# Microcontroller.net
KiCad netlist of a schematic drawn in Altium Designer
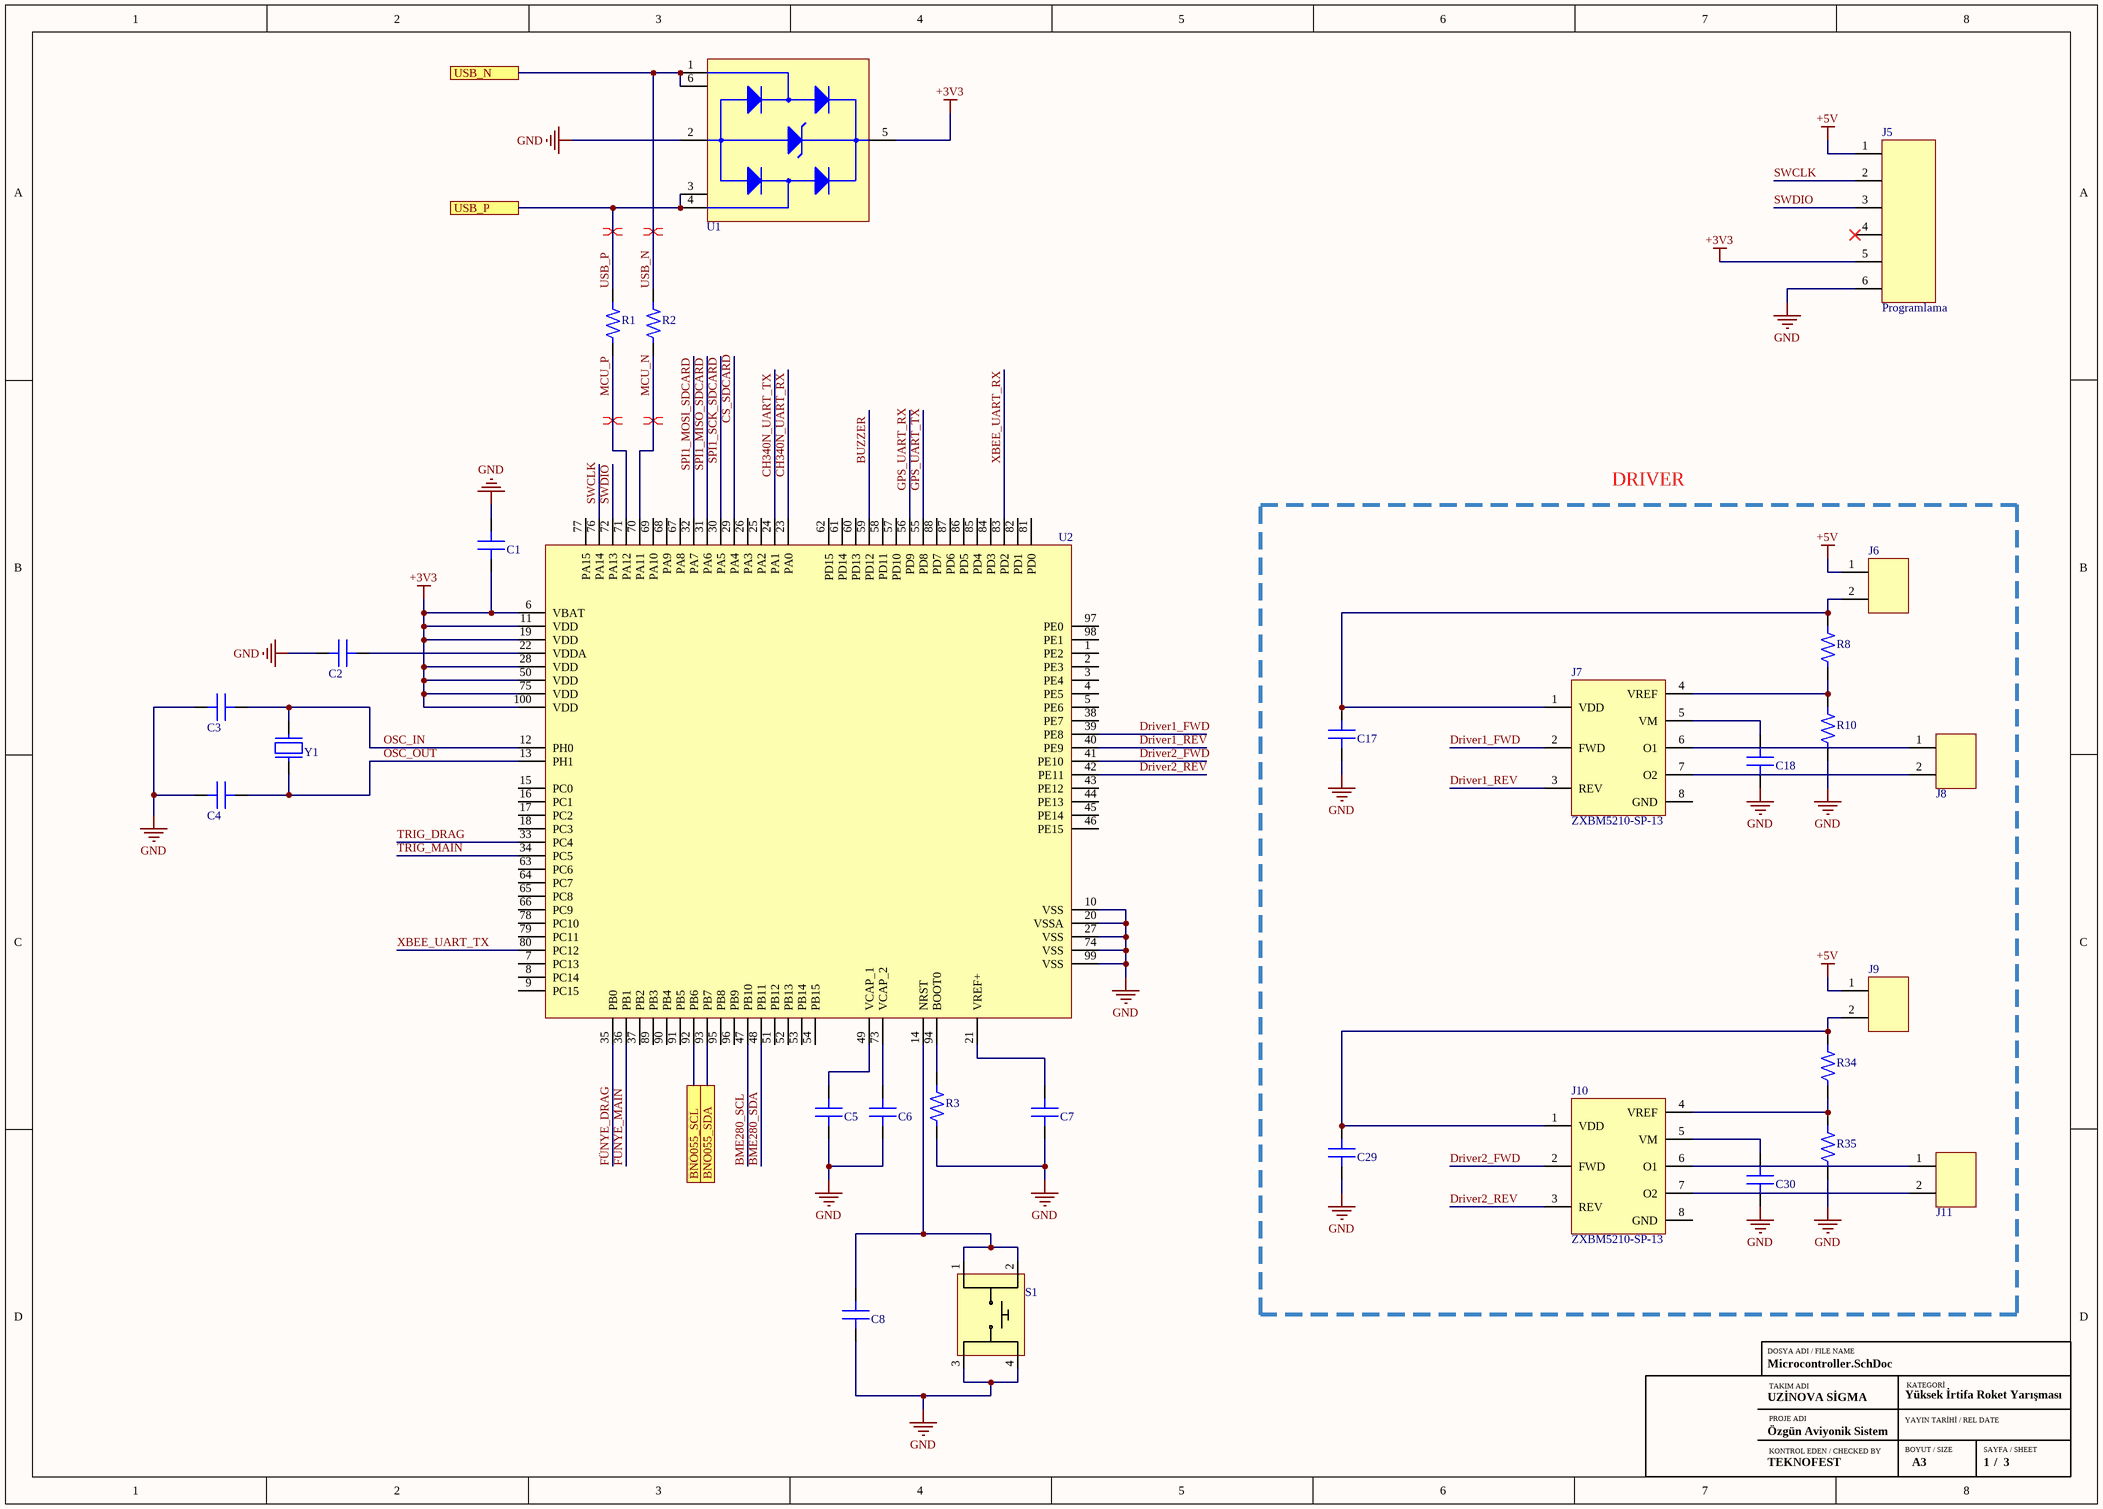
[diagram p0: Microcontroller.SchDoc]

(export (version "E")
  (design (tool "Eeschema 10.0.6"))
  (components
    (comp (ref "C1")
      (value "CAP CER 1uF 0805")
      (footprint "CAP_0805")
      (libsource (lib "ROKET_LIBRARY") (part "CAP CER 1uF 0805"))
    )
    (comp (ref "C2")
      (value "CAP CER 10nF 0805")
      (footprint "CAP_0805")
      (libsource (lib "ROKET_LIBRARY") (part "CAP CER 10nF 0805"))
    )
    (comp (ref "C3")
      (value "CAP CER 20pF 0805")
      (footprint "CAP_0805")
      (libsource (lib "ROKET_LIBRARY") (part "CAP CER 20pF 0805"))
    )
    (comp (ref "C4")
      (value "CAP CER 20pF 0805")
      (footprint "CAP_0805")
      (libsource (lib "ROKET_LIBRARY") (part "CAP CER 20pF 0805"))
    )
    (comp (ref "C5")
      (value "CAP CER 2.2uF 0805")
      (footprint "CAP_0805")
      (libsource (lib "ROKET_LIBRARY") (part "CAP CER 2.2uF 0805"))
    )
    (comp (ref "C6")
      (value "CAP CER 2.2uF 0805")
      (footprint "CAP_0805")
      (libsource (lib "ROKET_LIBRARY") (part "CAP CER 2.2uF 0805"))
    )
    (comp (ref "C7")
      (value "CAP CER 10nF 0805")
      (footprint "CAP_0805")
      (libsource (lib "ROKET_LIBRARY") (part "CAP CER 10nF 0805"))
    )
    (comp (ref "C8")
      (value "CAP CER 0.1uF 0805")
      (footprint "CAP_0805")
      (libsource (lib "ROKET_LIBRARY") (part "CAP CER 0.1uF 0805"))
    )
    (comp (ref "C17")
      (value "CAP CER 1uF 0805")
      (footprint "CAP_0805")
      (libsource (lib "ROKET_LIBRARY") (part "CAP CER 1uF 0805"))
    )
    (comp (ref "C18")
      (value "CAP CER 10uF 0805")
      (footprint "CAP_0805")
      (libsource (lib "ROKET_LIBRARY") (part "CAP CER 10uF 0805"))
    )
    (comp (ref "C29")
      (value "CAP CER 1uF 0805")
      (footprint "CAP_0805")
      (libsource (lib "ROKET_LIBRARY") (part "CAP CER 1uF 0805"))
    )
    (comp (ref "C30")
      (value "CAP CER 10uF 0805")
      (footprint "CAP_0805")
      (libsource (lib "ROKET_LIBRARY") (part "CAP CER 10uF 0805"))
    )
    (comp (ref "J5")
      (value "Programlama")
      (footprint "PPTC061LFBN-RC")
      (libsource (lib "ROKET_LIBRARY") (part "Programlama"))
    )
    (comp (ref "J6")
      (value "Mike Connector")
      (footprint "MIKE CONNECTOR")
      (libsource (lib "ROKET_LIBRARY") (part "Mike Connector"))
    )
    (comp (ref "J7")
      (value "ZXBM5210-SP-13")
      (footprint "SO-8EP")
      (description "ZXBM5210 Series 18 V 1.5 A Reversible DC Motor Drive with Speed Control-SOIC-8EP")
      (fields (field (name "MANUFACTURER") "Diodes"))
      (libsource (lib "Roket_Library") (part "Driver"))
    )
    (comp (ref "J8")
      (value "HEADER x2")
      (footprint "HEADER x2")
      (description "Conn Screw Type Terminal Block 2 POS 3.5mm Solder ST Thru-Hole 10A")
      (fields
        (field (name "MANUFACTURER") "On-Shore Technology")
        (field (name "MANUFACTURER PART NUMBER") "OSTTE020104")
      )
      (libsource (lib "ROKET_LIBRARY") (part "HEADER x2"))
    )
    (comp (ref "J9")
      (value "Mike Connector")
      (footprint "MIKE CONNECTOR")
      (libsource (lib "ROKET_LIBRARY") (part "Mike Connector"))
    )
    (comp (ref "J10")
      (value "ZXBM5210-SP-13")
      (footprint "SO-8EP")
      (description "ZXBM5210 Series 18 V 1.5 A Reversible DC Motor Drive with Speed Control-SOIC-8EP")
      (fields (field (name "MANUFACTURER") "Diodes"))
      (libsource (lib "Roket_Library") (part "Driver"))
    )
    (comp (ref "J11")
      (value "HEADER x2")
      (footprint "HEADER x2")
      (description "Conn Screw Type Terminal Block 2 POS 3.5mm Solder ST Thru-Hole 10A")
      (fields
        (field (name "MANUFACTURER") "On-Shore Technology")
        (field (name "MANUFACTURER PART NUMBER") "OSTTE020104")
      )
      (libsource (lib "ROKET_LIBRARY") (part "HEADER x2"))
    )
    (comp (ref "R1")
      (value "RES 15 OHM 0805")
      (footprint "RES_0805")
      (libsource (lib "ROKET_LIBRARY") (part "RES 15 OHM 0805"))
    )
    (comp (ref "R2")
      (value "RES 15 OHM 0805")
      (footprint "RES_0805")
      (libsource (lib "ROKET_LIBRARY") (part "RES 15 OHM 0805"))
    )
    (comp (ref "R3")
      (value "RES 10K OHM 0805")
      (footprint "RES_0805")
      (libsource (lib "ROKET_LIBRARY") (part "RES 10K OHM 0805"))
    )
    (comp (ref "R8")
      (value "RES 1K OHM 0805")
      (footprint "RES_0805")
      (libsource (lib "ROKET_LIBRARY") (part "RES 1K OHM 0805"))
    )
    (comp (ref "R10")
      (value "RES 1K OHM 0805")
      (footprint "RES_0805")
      (libsource (lib "ROKET_LIBRARY") (part "RES 1K OHM 0805"))
    )
    (comp (ref "R34")
      (value "RES 1K OHM 0805")
      (footprint "RES_0805")
      (libsource (lib "ROKET_LIBRARY") (part "RES 1K OHM 0805"))
    )
    (comp (ref "R35")
      (value "RES 1K OHM 0805")
      (footprint "RES_0805")
      (libsource (lib "ROKET_LIBRARY") (part "RES 1K OHM 0805"))
    )
    (comp (ref "S1")
      (value "PTS815 SJG 250 SMTR LFS")
      (footprint "BUTTON")
      (description "Switch Tactile N.O. SPST Button J-Bend 0.05A 12VDC 3.92N SMD T/R")
      (fields
        (field (name "MANUFACTURER") "ITT C&K")
        (field (name "MANUFACTURER PART NUMBER") "PTS815SJG250SMTRLFS")
      )
      (libsource (lib "ROKET_LIBRARY") (part "BUTTON"))
    )
    (comp (ref "U1")
      (value "USBLC6-2SC6")
      (footprint "SOT-23-6L")
      (description "TVS DIODE 5.25VWM 17VC SOT23-6")
      (fields (field (name "MANUFACTURER") "STMicroelectronics"))
      (libsource (lib "ROKET_LIBRARY") (part "USB PROTECTION"))
    )
    (comp (ref "U2")
      (value "STM32F407VGT6")
      (footprint "LQFP-100")
      (description "IC MCU 32BIT 1MB FLASH 100LQFP")
      (fields (field (name "MANUFACTURER") "STMicroelectronics"))
      (libsource (lib "ROKET_LIBRARY") (part "STM32F407VGT6"))
    )
    (comp (ref "Y1")
      (value "CRYSTAL 32.7680KHZ 12.5PF SMD")
      (footprint "CRYSTAL_ABS05")
      (description "Crystal 0.032768MHz ±20ppm (Tol) 12.5pF Flexural 90000Ohm 2-Pin CSMD T/R")
      (fields
        (field (name "MANUFACTURER") "Abracon")
        (field (name "MANUFACTURER PART NUMBER") "ABS05-32.768KHZ-T")
      )
      (libsource (lib "ROKET_LIBRARY") (part "CRYSTAL"))
    )
  )
  (nets
    (net (code "1") (name "+3V3") (class "Default")
      (node (ref "C1") (pin "1") (pinfunction "1_1") (pintype "passive"))
      (node (ref "J5") (pin "5") (pintype "passive"))
      (node (ref "U1") (pin "5") (pinfunction "VBUS_5") (pintype "power_in"))
      (node (ref "U2") (pin "100") (pinfunction "VDD_100") (pintype "passive"))
      (node (ref "U2") (pin "11") (pinfunction "VDD_11") (pintype "passive"))
      (node (ref "U2") (pin "19") (pinfunction "VDD_19") (pintype "passive"))
      (node (ref "U2") (pin "28") (pinfunction "VDD_28") (pintype "passive"))
      (node (ref "U2") (pin "50") (pinfunction "VDD_50") (pintype "passive"))
      (node (ref "U2") (pin "6") (pinfunction "VBAT_6") (pintype "passive"))
      (node (ref "U2") (pin "75") (pinfunction "VDD_75") (pintype "passive"))
    )
    (net (code "2") (name "+5V") (class "Default")
      (node (ref "J5") (pin "1") (pintype "passive"))
      (node (ref "J6") (pin "1") (pintype "passive"))
      (node (ref "J9") (pin "1") (pintype "passive"))
    )
    (net (code "3") (name "/BME280_SCL") (class "Default")
      (node (ref "U2") (pin "47") (pinfunction "PB10_47") (pintype "passive"))
    )
    (net (code "4") (name "/BME280_SDA") (class "Default")
      (node (ref "U2") (pin "48") (pinfunction "PB11_48") (pintype "passive"))
    )
    (net (code "5") (name "/BNO055_SCL") (class "Default")
      (node (ref "U2") (pin "92") (pinfunction "PB6_92") (pintype "passive"))
    )
    (net (code "6") (name "/BNO055_SDA") (class "Default")
      (node (ref "U2") (pin "93") (pinfunction "PB7_93") (pintype "passive"))
    )
    (net (code "7") (name "/BUZZER") (class "Default")
      (node (ref "U2") (pin "59") (pinfunction "PD12_59") (pintype "passive"))
    )
    (net (code "8") (name "/CH340N_UART_RX") (class "Default")
      (node (ref "U2") (pin "23") (pinfunction "PA0_23") (pintype "passive"))
    )
    (net (code "9") (name "/CH340N_UART_TX") (class "Default")
      (node (ref "U2") (pin "24") (pinfunction "PA1_24") (pintype "passive"))
    )
    (net (code "10") (name "/CS_SDCARD") (class "Default")
      (node (ref "U2") (pin "29") (pinfunction "PA4_29") (pintype "passive"))
    )
    (net (code "11") (name "/Driver1_FWD") (class "Default")
      (node (ref "J7") (pin "2") (pinfunction "FWD_2") (pintype "passive"))
      (node (ref "U2") (pin "39") (pinfunction "PE8_39") (pintype "passive"))
    )
    (net (code "12") (name "/Driver1_REV") (class "Default")
      (node (ref "J7") (pin "3") (pinfunction "REV_3") (pintype "passive"))
      (node (ref "U2") (pin "40") (pinfunction "PE9_40") (pintype "passive"))
    )
    (net (code "13") (name "/Driver2_FWD") (class "Default")
      (node (ref "J10") (pin "2") (pinfunction "FWD_2") (pintype "passive"))
      (node (ref "U2") (pin "41") (pinfunction "PE10_41") (pintype "passive"))
    )
    (net (code "14") (name "/Driver2_REV") (class "Default")
      (node (ref "J10") (pin "3") (pinfunction "REV_3") (pintype "passive"))
      (node (ref "U2") (pin "42") (pinfunction "PE11_42") (pintype "passive"))
    )
    (net (code "15") (name "/FÜNYE_DRAG") (class "Default")
      (node (ref "U2") (pin "35") (pinfunction "PB0_35") (pintype "passive"))
    )
    (net (code "16") (name "/FÜNYE_MAIN") (class "Default")
      (node (ref "U2") (pin "36") (pinfunction "PB1_36") (pintype "passive"))
    )
    (net (code "17") (name "/GPS_UART_RX") (class "Default")
      (node (ref "U2") (pin "56") (pinfunction "PD9_56") (pintype "passive"))
    )
    (net (code "18") (name "/GPS_UART_TX") (class "Default")
      (node (ref "U2") (pin "55") (pinfunction "PD8_55") (pintype "passive"))
    )
    (net (code "19") (name "/MCU_N") (class "Default")
      (node (ref "R2") (pin "1") (pinfunction "1_1") (pintype "passive"))
      (node (ref "U2") (pin "70") (pinfunction "PA11_70") (pintype "passive"))
    )
    (net (code "20") (name "/MCU_P") (class "Default")
      (node (ref "R1") (pin "1") (pinfunction "1_1") (pintype "passive"))
      (node (ref "U2") (pin "71") (pinfunction "PA12_71") (pintype "passive"))
    )
    (net (code "21") (name "/OSC_IN") (class "Default")
      (node (ref "C3") (pin "2") (pinfunction "2_2") (pintype "passive"))
      (node (ref "U2") (pin "12") (pinfunction "PH0_12") (pintype "passive"))
      (node (ref "Y1") (pin "2") (pinfunction "2_2") (pintype "passive"))
    )
    (net (code "22") (name "/OSC_OUT") (class "Default")
      (node (ref "C4") (pin "2") (pinfunction "2_2") (pintype "passive"))
      (node (ref "U2") (pin "13") (pinfunction "PH1_13") (pintype "passive"))
      (node (ref "Y1") (pin "1") (pinfunction "1_1") (pintype "passive"))
    )
    (net (code "23") (name "/SPI1_MISO_SDCARD") (class "Default")
      (node (ref "U2") (pin "31") (pinfunction "PA6_31") (pintype "passive"))
    )
    (net (code "24") (name "/SPI1_MOSI_SDCARD") (class "Default")
      (node (ref "U2") (pin "32") (pinfunction "PA7_32") (pintype "passive"))
    )
    (net (code "25") (name "/SPI1_SCK_SDCARD") (class "Default")
      (node (ref "U2") (pin "30") (pinfunction "PA5_30") (pintype "passive"))
    )
    (net (code "26") (name "/SWCLK") (class "Default")
      (node (ref "J5") (pin "2") (pintype "passive"))
      (node (ref "U2") (pin "76") (pinfunction "PA14_76") (pintype "passive"))
    )
    (net (code "27") (name "/SWDIO") (class "Default")
      (node (ref "J5") (pin "3") (pintype "passive"))
      (node (ref "U2") (pin "72") (pinfunction "PA13_72") (pintype "passive"))
    )
    (net (code "28") (name "/TRIG_DRAG") (class "Default")
      (node (ref "U2") (pin "33") (pinfunction "PC4_33") (pintype "passive"))
    )
    (net (code "29") (name "/TRIG_MAIN") (class "Default")
      (node (ref "U2") (pin "34") (pinfunction "PC5_34") (pintype "passive"))
    )
    (net (code "30") (name "/USB_N") (class "Default")
      (node (ref "R2") (pin "2") (pinfunction "2_2") (pintype "passive"))
      (node (ref "U1") (pin "1") (pinfunction "I/O1_IN_1") (pintype "passive"))
      (node (ref "U1") (pin "6") (pinfunction "I/O1_OUT_6") (pintype "passive"))
    )
    (net (code "31") (name "/USB_P") (class "Default")
      (node (ref "R1") (pin "2") (pinfunction "2_2") (pintype "passive"))
      (node (ref "U1") (pin "3") (pinfunction "I/O2_IN_3") (pintype "passive"))
      (node (ref "U1") (pin "4") (pinfunction "I/O2_OUT_4") (pintype "passive"))
    )
    (net (code "32") (name "/XBEE_UART_RX") (class "Default")
      (node (ref "U2") (pin "83") (pinfunction "PD2_83") (pintype "passive"))
    )
    (net (code "33") (name "/XBEE_UART_TX") (class "Default")
      (node (ref "U2") (pin "80") (pinfunction "PC12_80") (pintype "passive"))
    )
    (net (code "34") (name "GND") (class "Default")
      (node (ref "C1") (pin "2") (pinfunction "2_2") (pintype "passive"))
      (node (ref "C17") (pin "1") (pinfunction "1_1") (pintype "passive"))
      (node (ref "C18") (pin "1") (pinfunction "1_1") (pintype "passive"))
      (node (ref "C2") (pin "1") (pinfunction "1_1") (pintype "passive"))
      (node (ref "C29") (pin "1") (pinfunction "1_1") (pintype "passive"))
      (node (ref "C3") (pin "1") (pinfunction "1_1") (pintype "passive"))
      (node (ref "C30") (pin "1") (pinfunction "1_1") (pintype "passive"))
      (node (ref "C4") (pin "1") (pinfunction "1_1") (pintype "passive"))
      (node (ref "C5") (pin "1") (pinfunction "1_1") (pintype "passive"))
      (node (ref "C6") (pin "1") (pinfunction "1_1") (pintype "passive"))
      (node (ref "C7") (pin "1") (pinfunction "1_1") (pintype "passive"))
      (node (ref "C8") (pin "1") (pinfunction "1_1") (pintype "passive"))
      (node (ref "J5") (pin "6") (pintype "passive"))
      (node (ref "R10") (pin "1") (pinfunction "1_1") (pintype "passive"))
      (node (ref "R3") (pin "1") (pinfunction "1_1") (pintype "passive"))
      (node (ref "R35") (pin "1") (pinfunction "1_1") (pintype "passive"))
      (node (ref "S1") (pin "3") (pinfunction "3_3") (pintype "passive"))
      (node (ref "S1") (pin "4") (pinfunction "4_4") (pintype "passive"))
      (node (ref "U1") (pin "2") (pinfunction "GND_2") (pintype "power_in"))
      (node (ref "U2") (pin "10") (pinfunction "VSS_10") (pintype "passive"))
      (node (ref "U2") (pin "20") (pinfunction "VSSA_20") (pintype "passive"))
      (node (ref "U2") (pin "27") (pinfunction "VSS_27") (pintype "passive"))
      (node (ref "U2") (pin "74") (pinfunction "VSS_74") (pintype "passive"))
      (node (ref "U2") (pin "99") (pinfunction "VSS_99") (pintype "passive"))
    )
    (net (code "35") (name "Net-(J7-O1)") (class "Default")
      (node (ref "J7") (pin "6") (pinfunction "O1_6") (pintype "passive"))
      (node (ref "J8") (pin "1") (pinfunction "1_1") (pintype "passive"))
    )
    (net (code "36") (name "Net-(J7-O2)") (class "Default")
      (node (ref "J7") (pin "7") (pinfunction "O2_7") (pintype "passive"))
      (node (ref "J8") (pin "2") (pinfunction "2_2") (pintype "passive"))
    )
    (net (code "37") (name "Net-(J7-VDD)") (class "Default")
      (node (ref "C17") (pin "2") (pinfunction "2_2") (pintype "passive"))
      (node (ref "J6") (pin "2") (pintype "passive"))
      (node (ref "J7") (pin "1") (pinfunction "VDD_1") (pintype "passive"))
      (node (ref "R8") (pin "2") (pinfunction "2_2") (pintype "passive"))
    )
    (net (code "38") (name "Net-(J7-VM)") (class "Default")
      (node (ref "C18") (pin "2") (pinfunction "2_2") (pintype "passive"))
      (node (ref "J7") (pin "5") (pinfunction "VM_5") (pintype "passive"))
    )
    (net (code "39") (name "Net-(J7-VREF)") (class "Default")
      (node (ref "J7") (pin "4") (pinfunction "VREF_4") (pintype "passive"))
      (node (ref "R10") (pin "2") (pinfunction "2_2") (pintype "passive"))
      (node (ref "R8") (pin "1") (pinfunction "1_1") (pintype "passive"))
    )
    (net (code "40") (name "Net-(J10-O1)") (class "Default")
      (node (ref "J10") (pin "6") (pinfunction "O1_6") (pintype "passive"))
      (node (ref "J11") (pin "1") (pinfunction "1_1") (pintype "passive"))
    )
    (net (code "41") (name "Net-(J10-O2)") (class "Default")
      (node (ref "J10") (pin "7") (pinfunction "O2_7") (pintype "passive"))
      (node (ref "J11") (pin "2") (pinfunction "2_2") (pintype "passive"))
    )
    (net (code "42") (name "Net-(J10-VDD)") (class "Default")
      (node (ref "C29") (pin "2") (pinfunction "2_2") (pintype "passive"))
      (node (ref "J10") (pin "1") (pinfunction "VDD_1") (pintype "passive"))
      (node (ref "J9") (pin "2") (pintype "passive"))
      (node (ref "R34") (pin "2") (pinfunction "2_2") (pintype "passive"))
    )
    (net (code "43") (name "Net-(J10-VM)") (class "Default")
      (node (ref "C30") (pin "2") (pinfunction "2_2") (pintype "passive"))
      (node (ref "J10") (pin "5") (pinfunction "VM_5") (pintype "passive"))
    )
    (net (code "44") (name "Net-(J10-VREF)") (class "Default")
      (node (ref "J10") (pin "4") (pinfunction "VREF_4") (pintype "passive"))
      (node (ref "R34") (pin "1") (pinfunction "1_1") (pintype "passive"))
      (node (ref "R35") (pin "2") (pinfunction "2_2") (pintype "passive"))
    )
    (net (code "45") (name "Net-(U2-BOOT0)") (class "Default")
      (node (ref "R3") (pin "2") (pinfunction "2_2") (pintype "passive"))
      (node (ref "U2") (pin "94") (pinfunction "BOOT0_94") (pintype "passive"))
    )
    (net (code "46") (name "Net-(U2-NRST)") (class "Default")
      (node (ref "C8") (pin "2") (pinfunction "2_2") (pintype "passive"))
      (node (ref "S1") (pin "1") (pinfunction "1_1") (pintype "passive"))
      (node (ref "S1") (pin "2") (pinfunction "2_2") (pintype "passive"))
      (node (ref "U2") (pin "14") (pinfunction "NRST_14") (pintype "passive"))
    )
    (net (code "47") (name "Net-(U2-VCAP_1)") (class "Default")
      (node (ref "C5") (pin "2") (pinfunction "2_2") (pintype "passive"))
      (node (ref "U2") (pin "49") (pinfunction "VCAP_1_49") (pintype "passive"))
    )
    (net (code "48") (name "Net-(U2-VCAP_2)") (class "Default")
      (node (ref "C6") (pin "2") (pinfunction "2_2") (pintype "passive"))
      (node (ref "U2") (pin "73") (pinfunction "VCAP_2_73") (pintype "passive"))
    )
    (net (code "49") (name "Net-(U2-VDDA)") (class "Default")
      (node (ref "C2") (pin "2") (pinfunction "2_2") (pintype "passive"))
      (node (ref "U2") (pin "22") (pinfunction "VDDA_22") (pintype "passive"))
    )
    (net (code "50") (name "Net-(U2-VREF+)") (class "Default")
      (node (ref "C7") (pin "2") (pinfunction "2_2") (pintype "passive"))
      (node (ref "U2") (pin "21") (pinfunction "VREF+_21") (pintype "passive"))
    )
    (net (code "51") (name "unconnected-(J5-Pad4)") (class "Default")
      (node (ref "J5") (pin "4") (pintype "passive+no_connect"))
    )
    (net (code "52") (name "unconnected-(J7-GND-Pad8)") (class "Default")
      (node (ref "J7") (pin "8") (pinfunction "GND_8") (pintype "passive"))
    )
    (net (code "53") (name "unconnected-(J10-GND-Pad8)") (class "Default")
      (node (ref "J10") (pin "8") (pinfunction "GND_8") (pintype "passive"))
    )
    (net (code "54") (name "unconnected-(U2-PA2-Pad25)") (class "Default")
      (node (ref "U2") (pin "25") (pinfunction "PA2_25") (pintype "passive"))
    )
    (net (code "55") (name "unconnected-(U2-PA3-Pad26)") (class "Default")
      (node (ref "U2") (pin "26") (pinfunction "PA3_26") (pintype "passive"))
    )
    (net (code "56") (name "unconnected-(U2-PA8-Pad67)") (class "Default")
      (node (ref "U2") (pin "67") (pinfunction "PA8_67") (pintype "passive"))
    )
    (net (code "57") (name "unconnected-(U2-PA9-Pad68)") (class "Default")
      (node (ref "U2") (pin "68") (pinfunction "PA9_68") (pintype "passive"))
    )
    (net (code "58") (name "unconnected-(U2-PA10-Pad69)") (class "Default")
      (node (ref "U2") (pin "69") (pinfunction "PA10_69") (pintype "passive"))
    )
    (net (code "59") (name "unconnected-(U2-PA15-Pad77)") (class "Default")
      (node (ref "U2") (pin "77") (pinfunction "PA15_77") (pintype "passive"))
    )
    (net (code "60") (name "unconnected-(U2-PB2-Pad37)") (class "Default")
      (node (ref "U2") (pin "37") (pinfunction "PB2_37") (pintype "passive"))
    )
    (net (code "61") (name "unconnected-(U2-PB3-Pad89)") (class "Default")
      (node (ref "U2") (pin "89") (pinfunction "PB3_89") (pintype "passive"))
    )
    (net (code "62") (name "unconnected-(U2-PB4-Pad90)") (class "Default")
      (node (ref "U2") (pin "90") (pinfunction "PB4_90") (pintype "passive"))
    )
    (net (code "63") (name "unconnected-(U2-PB5-Pad91)") (class "Default")
      (node (ref "U2") (pin "91") (pinfunction "PB5_91") (pintype "passive"))
    )
    (net (code "64") (name "unconnected-(U2-PB8-Pad95)") (class "Default")
      (node (ref "U2") (pin "95") (pinfunction "PB8_95") (pintype "passive"))
    )
    (net (code "65") (name "unconnected-(U2-PB9-Pad96)") (class "Default")
      (node (ref "U2") (pin "96") (pinfunction "PB9_96") (pintype "passive"))
    )
    (net (code "66") (name "unconnected-(U2-PB12-Pad51)") (class "Default")
      (node (ref "U2") (pin "51") (pinfunction "PB12_51") (pintype "passive"))
    )
    (net (code "67") (name "unconnected-(U2-PB13-Pad52)") (class "Default")
      (node (ref "U2") (pin "52") (pinfunction "PB13_52") (pintype "passive"))
    )
    (net (code "68") (name "unconnected-(U2-PB14-Pad53)") (class "Default")
      (node (ref "U2") (pin "53") (pinfunction "PB14_53") (pintype "passive"))
    )
    (net (code "69") (name "unconnected-(U2-PB15-Pad54)") (class "Default")
      (node (ref "U2") (pin "54") (pinfunction "PB15_54") (pintype "passive"))
    )
    (net (code "70") (name "unconnected-(U2-PC0-Pad15)") (class "Default")
      (node (ref "U2") (pin "15") (pinfunction "PC0_15") (pintype "passive"))
    )
    (net (code "71") (name "unconnected-(U2-PC1-Pad16)") (class "Default")
      (node (ref "U2") (pin "16") (pinfunction "PC1_16") (pintype "passive"))
    )
    (net (code "72") (name "unconnected-(U2-PC2-Pad17)") (class "Default")
      (node (ref "U2") (pin "17") (pinfunction "PC2_17") (pintype "passive"))
    )
    (net (code "73") (name "unconnected-(U2-PC3-Pad18)") (class "Default")
      (node (ref "U2") (pin "18") (pinfunction "PC3_18") (pintype "passive"))
    )
    (net (code "74") (name "unconnected-(U2-PC6-Pad63)") (class "Default")
      (node (ref "U2") (pin "63") (pinfunction "PC6_63") (pintype "passive"))
    )
    (net (code "75") (name "unconnected-(U2-PC7-Pad64)") (class "Default")
      (node (ref "U2") (pin "64") (pinfunction "PC7_64") (pintype "passive"))
    )
    (net (code "76") (name "unconnected-(U2-PC8-Pad65)") (class "Default")
      (node (ref "U2") (pin "65") (pinfunction "PC8_65") (pintype "passive"))
    )
    (net (code "77") (name "unconnected-(U2-PC9-Pad66)") (class "Default")
      (node (ref "U2") (pin "66") (pinfunction "PC9_66") (pintype "passive"))
    )
    (net (code "78") (name "unconnected-(U2-PC10-Pad78)") (class "Default")
      (node (ref "U2") (pin "78") (pinfunction "PC10_78") (pintype "passive"))
    )
    (net (code "79") (name "unconnected-(U2-PC11-Pad79)") (class "Default")
      (node (ref "U2") (pin "79") (pinfunction "PC11_79") (pintype "passive"))
    )
    (net (code "80") (name "unconnected-(U2-PC13-Pad7)") (class "Default")
      (node (ref "U2") (pin "7") (pinfunction "PC13_7") (pintype "passive"))
    )
    (net (code "81") (name "unconnected-(U2-PC14-Pad8)") (class "Default")
      (node (ref "U2") (pin "8") (pinfunction "PC14_8") (pintype "passive"))
    )
    (net (code "82") (name "unconnected-(U2-PC15-Pad9)") (class "Default")
      (node (ref "U2") (pin "9") (pinfunction "PC15_9") (pintype "passive"))
    )
    (net (code "83") (name "unconnected-(U2-PD0-Pad81)") (class "Default")
      (node (ref "U2") (pin "81") (pinfunction "PD0_81") (pintype "passive"))
    )
    (net (code "84") (name "unconnected-(U2-PD1-Pad82)") (class "Default")
      (node (ref "U2") (pin "82") (pinfunction "PD1_82") (pintype "passive"))
    )
    (net (code "85") (name "unconnected-(U2-PD3-Pad84)") (class "Default")
      (node (ref "U2") (pin "84") (pinfunction "PD3_84") (pintype "passive"))
    )
    (net (code "86") (name "unconnected-(U2-PD4-Pad85)") (class "Default")
      (node (ref "U2") (pin "85") (pinfunction "PD4_85") (pintype "passive"))
    )
    (net (code "87") (name "unconnected-(U2-PD5-Pad86)") (class "Default")
      (node (ref "U2") (pin "86") (pinfunction "PD5_86") (pintype "passive"))
    )
    (net (code "88") (name "unconnected-(U2-PD6-Pad87)") (class "Default")
      (node (ref "U2") (pin "87") (pinfunction "PD6_87") (pintype "passive"))
    )
    (net (code "89") (name "unconnected-(U2-PD7-Pad88)") (class "Default")
      (node (ref "U2") (pin "88") (pinfunction "PD7_88") (pintype "passive"))
    )
    (net (code "90") (name "unconnected-(U2-PD10-Pad57)") (class "Default")
      (node (ref "U2") (pin "57") (pinfunction "PD10_57") (pintype "passive"))
    )
    (net (code "91") (name "unconnected-(U2-PD11-Pad58)") (class "Default")
      (node (ref "U2") (pin "58") (pinfunction "PD11_58") (pintype "passive"))
    )
    (net (code "92") (name "unconnected-(U2-PD13-Pad60)") (class "Default")
      (node (ref "U2") (pin "60") (pinfunction "PD13_60") (pintype "passive"))
    )
    (net (code "93") (name "unconnected-(U2-PD14-Pad61)") (class "Default")
      (node (ref "U2") (pin "61") (pinfunction "PD14_61") (pintype "passive"))
    )
    (net (code "94") (name "unconnected-(U2-PD15-Pad62)") (class "Default")
      (node (ref "U2") (pin "62") (pinfunction "PD15_62") (pintype "passive"))
    )
    (net (code "95") (name "unconnected-(U2-PE0-Pad97)") (class "Default")
      (node (ref "U2") (pin "97") (pinfunction "PE0_97") (pintype "passive"))
    )
    (net (code "96") (name "unconnected-(U2-PE1-Pad98)") (class "Default")
      (node (ref "U2") (pin "98") (pinfunction "PE1_98") (pintype "passive"))
    )
    (net (code "97") (name "unconnected-(U2-PE2-Pad1)") (class "Default")
      (node (ref "U2") (pin "1") (pinfunction "PE2_1") (pintype "passive"))
    )
    (net (code "98") (name "unconnected-(U2-PE3-Pad2)") (class "Default")
      (node (ref "U2") (pin "2") (pinfunction "PE3_2") (pintype "passive"))
    )
    (net (code "99") (name "unconnected-(U2-PE4-Pad3)") (class "Default")
      (node (ref "U2") (pin "3") (pinfunction "PE4_3") (pintype "passive"))
    )
    (net (code "100") (name "unconnected-(U2-PE5-Pad4)") (class "Default")
      (node (ref "U2") (pin "4") (pinfunction "PE5_4") (pintype "passive"))
    )
    (net (code "101") (name "unconnected-(U2-PE6-Pad5)") (class "Default")
      (node (ref "U2") (pin "5") (pinfunction "PE6_5") (pintype "passive"))
    )
    (net (code "102") (name "unconnected-(U2-PE7-Pad38)") (class "Default")
      (node (ref "U2") (pin "38") (pinfunction "PE7_38") (pintype "passive"))
    )
    (net (code "103") (name "unconnected-(U2-PE12-Pad43)") (class "Default")
      (node (ref "U2") (pin "43") (pinfunction "PE12_43") (pintype "passive"))
    )
    (net (code "104") (name "unconnected-(U2-PE13-Pad44)") (class "Default")
      (node (ref "U2") (pin "44") (pinfunction "PE13_44") (pintype "passive"))
    )
    (net (code "105") (name "unconnected-(U2-PE14-Pad45)") (class "Default")
      (node (ref "U2") (pin "45") (pinfunction "PE14_45") (pintype "passive"))
    )
    (net (code "106") (name "unconnected-(U2-PE15-Pad46)") (class "Default")
      (node (ref "U2") (pin "46") (pinfunction "PE15_46") (pintype "passive"))
    )
  )
)
